# Active_LPF_HPF_Sch.net
KiCad netlist of a schematic drawn in Altium Designer
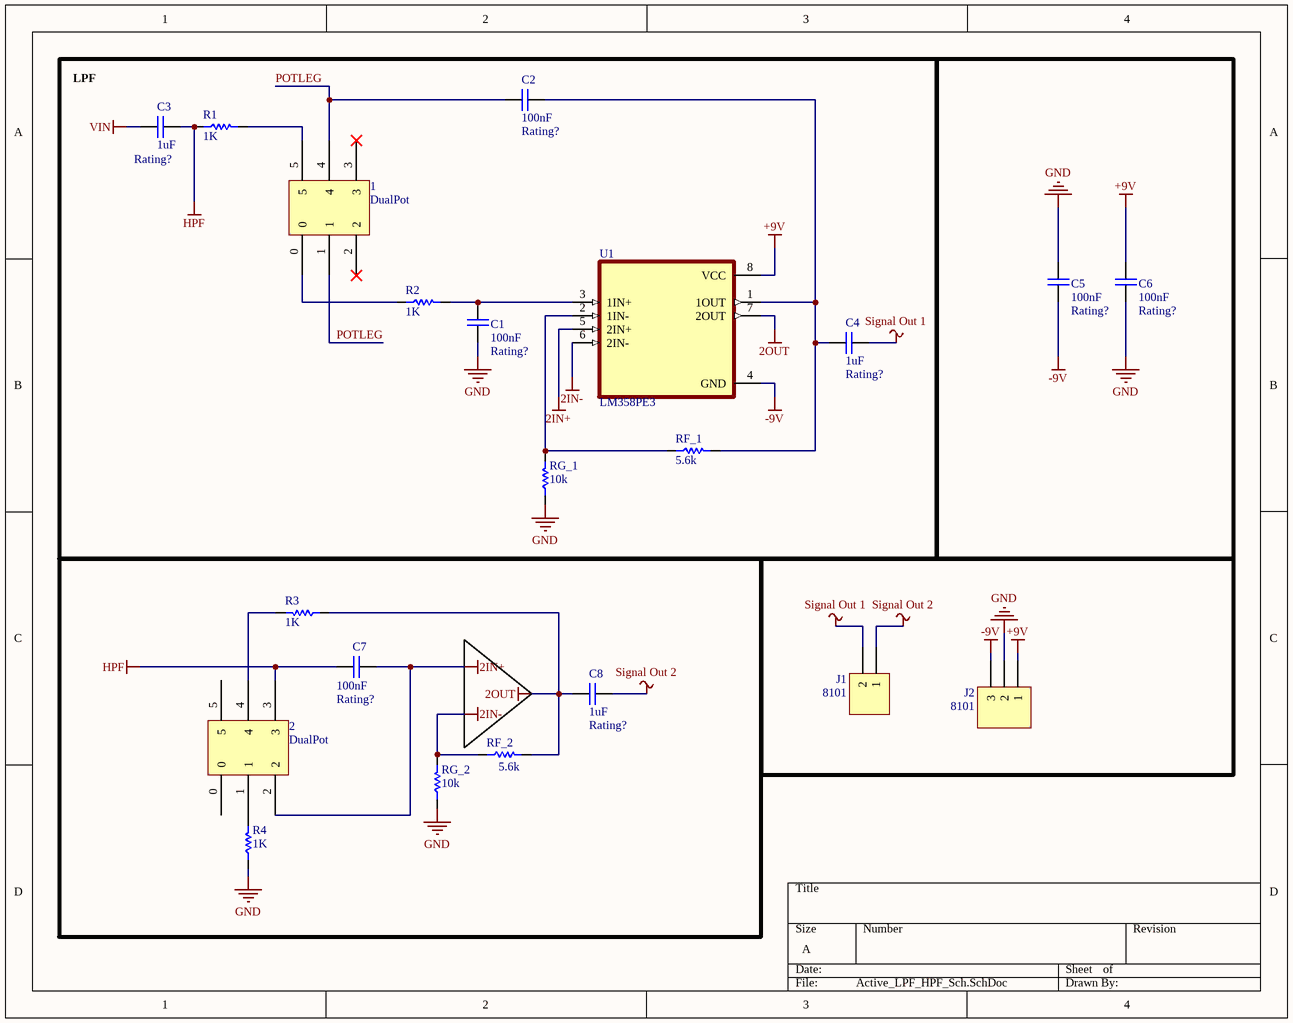
[diagram p0: Active_LPF_HPF_Sch.SchDoc]

(export (version "E")
  (design (tool "Eeschema 10.0.6"))
  (components
    (comp (ref "1") (value "DualPot") (footprint "DualPot") (libsource (lib "DualPot") (part "DualPot")))
    (comp (ref "2") (value "DualPot") (footprint "DualPot") (libsource (lib "DualPot") (part "DualPot")))
    (comp (ref "C1")
      (value "100nF")
      (footprint "Cap")
      (description "Multi layer capacitor")
      (fields (field (name "RATING") "Rating?") (field (name "VALIDATION") "Valid"))
      (libsource (lib "aKaReZa") (part "Cap_Multi_THT"))
    )
    (comp (ref "C2")
      (value "100nF")
      (footprint "Cap")
      (description "Multi layer capacitor")
      (fields (field (name "RATING") "Rating?") (field (name "VALIDATION") "Valid"))
      (libsource (lib "aKaReZa") (part "Cap_Multi_THT"))
    )
    (comp (ref "C3")
      (value "1uF")
      (footprint "Cap")
      (description "Multi layer capacitor")
      (fields (field (name "RATING") "Rating?") (field (name "VALIDATION") "Valid"))
      (libsource (lib "aKaReZa") (part "Cap_Multi_THT"))
    )
    (comp (ref "C4")
      (value "1uF")
      (footprint "Cap")
      (description "Multi layer capacitor")
      (fields (field (name "RATING") "Rating?") (field (name "VALIDATION") "Valid"))
      (libsource (lib "aKaReZa") (part "Cap_Multi_THT"))
    )
    (comp (ref "C5")
      (value "100nF")
      (footprint "Cap")
      (description "Multi layer capacitor")
      (fields (field (name "RATING") "Rating?") (field (name "VALIDATION") "Valid"))
      (libsource (lib "aKaReZa") (part "Cap_Multi_THT"))
    )
    (comp (ref "C6")
      (value "100nF")
      (footprint "Cap")
      (description "Multi layer capacitor")
      (fields (field (name "RATING") "Rating?") (field (name "VALIDATION") "Valid"))
      (libsource (lib "aKaReZa") (part "Cap_Multi_THT"))
    )
    (comp (ref "C7")
      (value "100nF")
      (footprint "Cap")
      (description "Multi layer capacitor")
      (fields (field (name "RATING") "Rating?") (field (name "VALIDATION") "Valid"))
      (libsource (lib "aKaReZa") (part "Cap_Multi_THT"))
    )
    (comp (ref "C8")
      (value "1uF")
      (footprint "Cap")
      (description "Multi layer capacitor")
      (fields (field (name "RATING") "Rating?") (field (name "VALIDATION") "Valid"))
      (libsource (lib "aKaReZa") (part "Cap_Multi_THT"))
    )
    (comp (ref "J1")
      (value "2")
      (footprint "HDR_THT_2F_2.54mm")
      (description "Header, single row, 2 pin")
      (fields (field (name "INFLOW") "8101") (field (name "VALIDATION") "NT"))
      (libsource (lib "aKaReZa") (part "Con_FPH_2x1_V_THT_2.54"))
    )
    (comp (ref "J2")
      (value "3")
      (footprint "HDR_THT_3F_2.54mm")
      (description "Header, single row, 3 pin")
      (fields (field (name "INFLOW") "8101") (field (name "VALIDATION") "NT"))
      (libsource (lib "aKaReZa") (part "Con_FPH_3x1_V_THT_2.54"))
    )
    (comp (ref "R1")
      (value "1K")
      (footprint "Res-(1/4)")
      (description "Resistor")
      (fields (field (name "VALIDATION") "Valid"))
      (libsource (lib "aKaReZa") (part "Res_THT"))
    )
    (comp (ref "R2")
      (value "1K")
      (footprint "Res-(1/4)")
      (description "Resistor")
      (fields (field (name "VALIDATION") "Valid"))
      (libsource (lib "aKaReZa") (part "Res_THT"))
    )
    (comp (ref "R3")
      (value "1K")
      (footprint "Res-(1/4)")
      (description "Resistor")
      (fields (field (name "VALIDATION") "Valid"))
      (libsource (lib "aKaReZa") (part "Res_THT"))
    )
    (comp (ref "R4")
      (value "1K")
      (footprint "Res-(1/4)")
      (description "Resistor")
      (fields (field (name "VALIDATION") "Valid"))
      (libsource (lib "aKaReZa") (part "Res_THT"))
    )
    (comp (ref "RF_1")
      (value "5.6k")
      (footprint "Res-(1/4)")
      (description "Resistor")
      (fields (field (name "VALIDATION") "Valid"))
      (libsource (lib "aKaReZa") (part "Res_THT"))
    )
    (comp (ref "RF_2")
      (value "5.6k")
      (footprint "Res-(1/4)")
      (description "Resistor")
      (fields (field (name "VALIDATION") "Valid"))
      (libsource (lib "aKaReZa") (part "Res_THT"))
    )
    (comp (ref "RG_1")
      (value "10k")
      (footprint "Res-(1/4)")
      (description "Resistor")
      (fields (field (name "VALIDATION") "Valid"))
      (libsource (lib "aKaReZa") (part "Res_THT"))
    )
    (comp (ref "RG_2")
      (value "10k")
      (footprint "Res-(1/4)")
      (description "Resistor")
      (fields (field (name "VALIDATION") "Valid"))
      (libsource (lib "aKaReZa") (part "Res_THT"))
    )
    (comp (ref "U1")
      (value "LM358PE3")
      (footprint "DIP794W45P254L959H508Q8")
      (description "Dual, 30-V, 700-kHz operational amplifier")
      (fields (field (name "MF") "Texas Instruments"))
      (libsource (lib "LM358PE3") (part "LM358PE3"))
    )
  )
  (nets
    (net (code "1") (name "+9V") (class "Default")
      (node (ref "C6") (pin "2") (pinfunction "2_2") (pintype "passive"))
      (node (ref "J2") (pin "1") (pinfunction "1_1") (pintype "passive"))
      (node (ref "U1") (pin "8") (pinfunction "VCC_8") (pintype "power_in"))
    )
    (net (code "2") (name "-9V") (class "Default")
      (node (ref "C5") (pin "1") (pinfunction "1_1") (pintype "passive"))
      (node (ref "J2") (pin "3") (pinfunction "3_3") (pintype "passive"))
      (node (ref "U1") (pin "4") (pinfunction "GND_4") (pintype "power_in"))
    )
    (net (code "3") (name "/POTLEG") (class "Default")
      (node (ref "1") (pin "1") (pinfunction "1_1") (pintype "passive"))
      (node (ref "1") (pin "4") (pinfunction "4_4") (pintype "passive"))
      (node (ref "C2") (pin "1") (pinfunction "1_1") (pintype "passive"))
    )
    (net (code "4") (name "2IN+") (class "Default")
      (node (ref "2") (pin "2") (pinfunction "2_2") (pintype "passive"))
      (node (ref "C7") (pin "2") (pinfunction "2_2") (pintype "passive"))
      (node (ref "U1") (pin "5") (pinfunction "2IN+_5") (pintype "input"))
    )
    (net (code "5") (name "2IN-") (class "Default")
      (node (ref "RF_2") (pin "1") (pinfunction "1_1") (pintype "passive"))
      (node (ref "RG_2") (pin "2") (pinfunction "2_2") (pintype "passive"))
      (node (ref "U1") (pin "6") (pinfunction "2IN-_6") (pintype "input"))
    )
    (net (code "6") (name "2OUT") (class "Default")
      (node (ref "C8") (pin "1") (pinfunction "1_1") (pintype "passive"))
      (node (ref "R3") (pin "1") (pinfunction "1_1") (pintype "passive"))
      (node (ref "RF_2") (pin "2") (pinfunction "2_2") (pintype "passive"))
      (node (ref "U1") (pin "7") (pinfunction "2OUT_7") (pintype "output"))
    )
    (net (code "7") (name "GND") (class "Default")
      (node (ref "C1") (pin "2") (pinfunction "2_2") (pintype "passive"))
      (node (ref "C5") (pin "2") (pinfunction "2_2") (pintype "passive"))
      (node (ref "C6") (pin "1") (pinfunction "1_1") (pintype "passive"))
      (node (ref "J2") (pin "2") (pinfunction "2_2") (pintype "passive"))
      (node (ref "R4") (pin "1") (pinfunction "1_1") (pintype "passive"))
      (node (ref "RG_1") (pin "1") (pinfunction "1_1") (pintype "passive"))
      (node (ref "RG_2") (pin "1") (pinfunction "1_1") (pintype "passive"))
    )
    (net (code "8") (name "HPF") (class "Default")
      (node (ref "2") (pin "3") (pinfunction "3_3") (pintype "passive"))
      (node (ref "C3") (pin "2") (pinfunction "2_2") (pintype "passive"))
      (node (ref "C7") (pin "1") (pinfunction "1_1") (pintype "passive"))
      (node (ref "R1") (pin "1") (pinfunction "1_1") (pintype "passive"))
    )
    (net (code "9") (name "Net-(1-Pad0)") (class "Default")
      (node (ref "1") (pin "0") (pinfunction "0_0") (pintype "passive"))
      (node (ref "R2") (pin "1") (pinfunction "1_1") (pintype "passive"))
    )
    (net (code "10") (name "Net-(1-Pad5)") (class "Default")
      (node (ref "1") (pin "5") (pinfunction "5_5") (pintype "passive"))
      (node (ref "R1") (pin "2") (pinfunction "2_2") (pintype "passive"))
    )
    (net (code "11") (name "Net-(2-Pad1)") (class "Default")
      (node (ref "2") (pin "1") (pinfunction "1_1") (pintype "passive"))
      (node (ref "R4") (pin "2") (pinfunction "2_2") (pintype "passive"))
    )
    (net (code "12") (name "Net-(2-Pad4)") (class "Default")
      (node (ref "2") (pin "4") (pinfunction "4_4") (pintype "passive"))
      (node (ref "R3") (pin "2") (pinfunction "2_2") (pintype "passive"))
    )
    (net (code "13") (name "Net-(U1-1IN+)") (class "Default")
      (node (ref "C1") (pin "1") (pinfunction "1_1") (pintype "passive"))
      (node (ref "R2") (pin "2") (pinfunction "2_2") (pintype "passive"))
      (node (ref "U1") (pin "3") (pinfunction "1IN+_3") (pintype "input"))
    )
    (net (code "14") (name "Net-(U1-1IN-)") (class "Default")
      (node (ref "RF_1") (pin "1") (pinfunction "1_1") (pintype "passive"))
      (node (ref "RG_1") (pin "2") (pinfunction "2_2") (pintype "passive"))
      (node (ref "U1") (pin "2") (pinfunction "1IN-_2") (pintype "input"))
    )
    (net (code "15") (name "Net-(U1-1OUT)") (class "Default")
      (node (ref "C2") (pin "2") (pinfunction "2_2") (pintype "passive"))
      (node (ref "C4") (pin "1") (pinfunction "1_1") (pintype "passive"))
      (node (ref "RF_1") (pin "2") (pinfunction "2_2") (pintype "passive"))
      (node (ref "U1") (pin "1") (pinfunction "1OUT_1") (pintype "output"))
    )
    (net (code "16") (name "Signal Out 1") (class "Default")
      (node (ref "C4") (pin "2") (pinfunction "2_2") (pintype "passive"))
      (node (ref "J1") (pin "2") (pinfunction "2_2") (pintype "passive"))
    )
    (net (code "17") (name "Signal Out 2") (class "Default")
      (node (ref "C8") (pin "2") (pinfunction "2_2") (pintype "passive"))
      (node (ref "J1") (pin "1") (pinfunction "1_1") (pintype "passive"))
    )
    (net (code "18") (name "VIN") (class "Default")
      (node (ref "C3") (pin "1") (pinfunction "1_1") (pintype "passive"))
    )
    (net (code "19") (name "unconnected-(1-Pad2)") (class "Default")
      (node (ref "1") (pin "2") (pinfunction "2_2") (pintype "passive+no_connect"))
    )
    (net (code "20") (name "unconnected-(1-Pad3)") (class "Default")
      (node (ref "1") (pin "3") (pinfunction "3_3") (pintype "passive+no_connect"))
    )
    (net (code "21") (name "unconnected-(2-Pad0)") (class "Default")
      (node (ref "2") (pin "0") (pinfunction "0_0") (pintype "passive"))
    )
    (net (code "22") (name "unconnected-(2-Pad5)") (class "Default")
      (node (ref "2") (pin "5") (pinfunction "5_5") (pintype "passive"))
    )
  )
)
